# naiLED_eagle.net
KiCad netlist of a schematic drawn in EAGLE
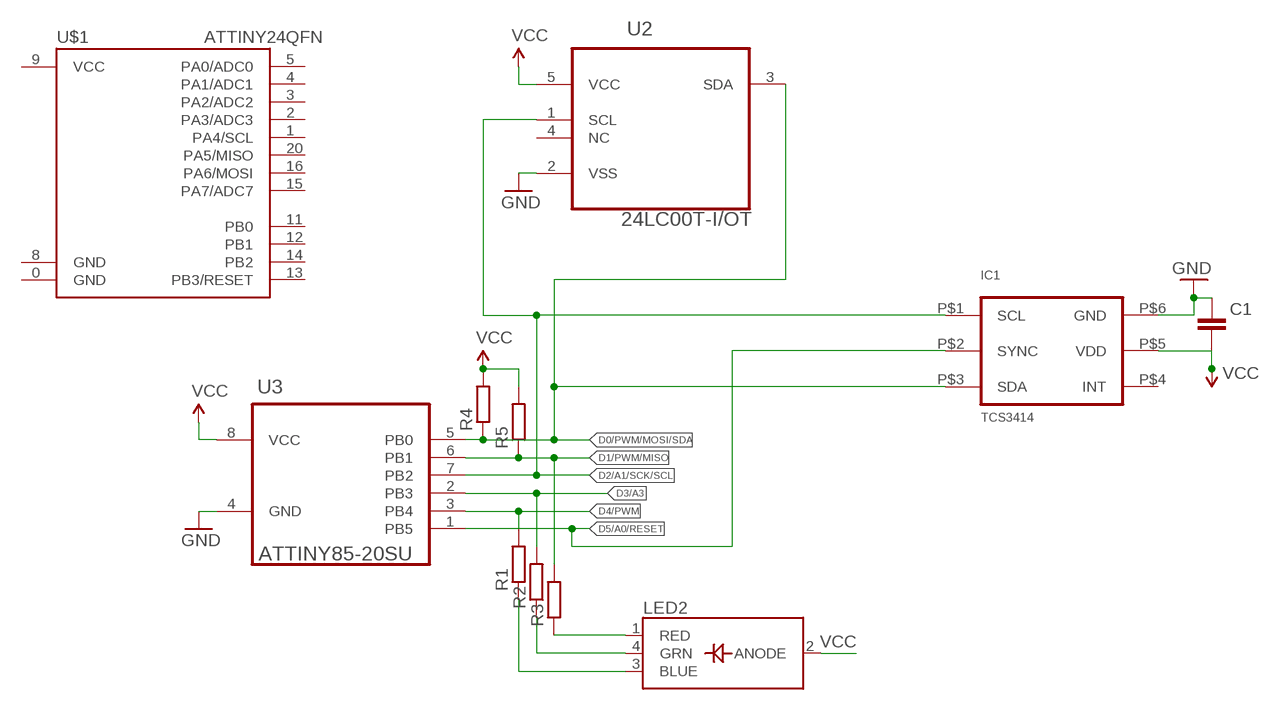
[diagram p0: schematic, sheet 1]

(export (version "E")
  (design (tool "Eeschema 10.0.6"))
  (components
    (comp (ref "C1")
      (value "CAPACITOR_NPOL-0402")
      (footprint "eagle-import:C402")
      (libsource (lib "eagle-import") (part "CAPACITOR_NPOL-0402"))
    )
    (comp (ref "IC1")
      (value "TCS3414")
      (footprint "eagle-import:DFN-6PIN")
      (libsource (lib "eagle-import") (part "TCS3414"))
    )
    (comp (ref "LED2")
      (value "LED_RGB_PLCC4")
      (footprint "eagle-import:RGBLED_PLCC4")
      (libsource (lib "eagle-import") (part "LED_RGB_PLCC4"))
    )
    (comp (ref "R1")
      (value "RESISTOR-0402")
      (footprint "eagle-import:R402")
      (libsource (lib "eagle-import") (part "RESISTOR-0402"))
    )
    (comp (ref "R2")
      (value "RESISTOR-0402")
      (footprint "eagle-import:R402")
      (libsource (lib "eagle-import") (part "RESISTOR-0402"))
    )
    (comp (ref "R3")
      (value "RESISTOR-0402")
      (footprint "eagle-import:R402")
      (libsource (lib "eagle-import") (part "RESISTOR-0402"))
    )
    (comp (ref "R4")
      (value "RESISTOR-0402")
      (footprint "eagle-import:R402")
      (libsource (lib "eagle-import") (part "RESISTOR-0402"))
    )
    (comp (ref "R5")
      (value "RESISTOR-0402")
      (footprint "eagle-import:R402")
      (libsource (lib "eagle-import") (part "RESISTOR-0402"))
    )
    (comp (ref "U$1")
      (value "ATTINY24QFN")
      (footprint "eagle-import:QFN20")
      (libsource (lib "eagle-import") (part "ATTINY24QFN"))
    )
    (comp (ref "U2")
      (value "24LC00T-I/OT")
      (footprint "eagle-import:SOT95P290X145-5N")
      (fields (field (name "MPN") "24LC00T-I/OT "))
      (libsource (lib "eagle-import") (part "24LC00T-I/OT"))
    )
    (comp (ref "U3")
      (value "ATTINY85-20SU")
      (footprint "eagle-import:SOIC127P798X216-8N")
      (libsource (lib "eagle-import") (part "ATTINY85-20SU"))
    )
  )
  (nets
    (net (code "1") (name "D0{slash}PWM{slash}MOSI{slash}SDA") (class "Default")
      (node (ref "IC1") (pin "P$3") (pinfunction "SDA_P$3") (pintype "bidirectional"))
      (node (ref "R4") (pin "1") (pinfunction "1_1") (pintype "passive"))
      (node (ref "U2") (pin "3") (pinfunction "SDA_3") (pintype "bidirectional"))
      (node (ref "U3") (pin "5") (pinfunction "PB0_5") (pintype "bidirectional"))
    )
    (net (code "2") (name "D1{slash}PWM{slash}MISO") (class "Default")
      (node (ref "R3") (pin "2") (pinfunction "2_2") (pintype "passive"))
      (node (ref "R5") (pin "1") (pinfunction "1_1") (pintype "passive"))
      (node (ref "U3") (pin "6") (pinfunction "PB1_6") (pintype "bidirectional"))
    )
    (net (code "3") (name "D2{slash}A1{slash}SCK{slash}SCL") (class "Default")
      (node (ref "IC1") (pin "P$1") (pinfunction "SCL_P$1") (pintype "bidirectional"))
      (node (ref "U2") (pin "1") (pinfunction "SCL_1") (pintype "input"))
      (node (ref "U3") (pin "7") (pinfunction "PB2_7") (pintype "bidirectional"))
    )
    (net (code "4") (name "D3{slash}A3") (class "Default")
      (node (ref "R2") (pin "2") (pinfunction "2_2") (pintype "passive"))
      (node (ref "U3") (pin "2") (pinfunction "PB3_2") (pintype "bidirectional"))
    )
    (net (code "5") (name "D4{slash}PWM") (class "Default")
      (node (ref "R1") (pin "2") (pinfunction "2_2") (pintype "passive"))
      (node (ref "U3") (pin "3") (pinfunction "PB4_3") (pintype "bidirectional"))
    )
    (net (code "6") (name "D5{slash}A0{slash}RESET") (class "Default")
      (node (ref "IC1") (pin "P$2") (pinfunction "SYNC_P$2") (pintype "bidirectional"))
      (node (ref "U3") (pin "1") (pinfunction "PB5_1") (pintype "bidirectional"))
    )
    (net (code "7") (name "GND") (class "Default")
      (node (ref "C1") (pin "2") (pinfunction "2_2") (pintype "passive"))
      (node (ref "IC1") (pin "P$6") (pinfunction "GND_P$6") (pintype "bidirectional"))
      (node (ref "U2") (pin "2") (pinfunction "VSS_2") (pintype "passive"))
      (node (ref "U3") (pin "4") (pinfunction "GND_4") (pintype "passive"))
    )
    (net (code "8") (name "Net-(LED2-BLUE)") (class "Default")
      (node (ref "LED2") (pin "3") (pinfunction "BLUE_3") (pintype "bidirectional"))
      (node (ref "R1") (pin "1") (pinfunction "1_1") (pintype "passive"))
    )
    (net (code "9") (name "Net-(LED2-GRN)") (class "Default")
      (node (ref "LED2") (pin "4") (pinfunction "GRN_4") (pintype "bidirectional"))
      (node (ref "R2") (pin "1") (pinfunction "1_1") (pintype "passive"))
    )
    (net (code "10") (name "Net-(LED2-RED)") (class "Default")
      (node (ref "LED2") (pin "1") (pinfunction "RED_1") (pintype "bidirectional"))
      (node (ref "R3") (pin "1") (pinfunction "1_1") (pintype "passive"))
    )
    (net (code "11") (name "VCC") (class "Default")
      (node (ref "C1") (pin "1") (pinfunction "1_1") (pintype "passive"))
      (node (ref "IC1") (pin "P$5") (pinfunction "VDD_P$5") (pintype "bidirectional"))
      (node (ref "LED2") (pin "2") (pinfunction "ANODE_2") (pintype "power_in"))
      (node (ref "R4") (pin "2") (pinfunction "2_2") (pintype "passive"))
      (node (ref "R5") (pin "2") (pinfunction "2_2") (pintype "passive"))
      (node (ref "U2") (pin "5") (pinfunction "VCC_5") (pintype "power_in"))
      (node (ref "U3") (pin "8") (pinfunction "VCC_8") (pintype "power_in"))
    )
    (net (code "12") (name "unconnected-(IC1-INT-PadP$4)") (class "Default")
      (node (ref "IC1") (pin "P$4") (pinfunction "INT_P$4") (pintype "bidirectional"))
    )
    (net (code "13") (name "unconnected-(U$1-GND-Pad0)") (class "Default")
      (node (ref "U$1") (pin "0") (pinfunction "GND_0") (pintype "bidirectional"))
    )
    (net (code "14") (name "unconnected-(U$1-GND-Pad8)") (class "Default")
      (node (ref "U$1") (pin "8") (pinfunction "GND_8") (pintype "bidirectional"))
    )
    (net (code "15") (name "unconnected-(U$1-PA0{slash}ADC0-Pad5)") (class "Default")
      (node (ref "U$1") (pin "5") (pinfunction "PA0/ADC0_5") (pintype "bidirectional"))
    )
    (net (code "16") (name "unconnected-(U$1-PA1{slash}ADC1-Pad4)") (class "Default")
      (node (ref "U$1") (pin "4") (pinfunction "PA1/ADC1_4") (pintype "bidirectional"))
    )
    (net (code "17") (name "unconnected-(U$1-PA2{slash}ADC2-Pad3)") (class "Default")
      (node (ref "U$1") (pin "3") (pinfunction "PA2/ADC2_3") (pintype "bidirectional"))
    )
    (net (code "18") (name "unconnected-(U$1-PA3{slash}ADC3-Pad2)") (class "Default")
      (node (ref "U$1") (pin "2") (pinfunction "PA3/ADC3_2") (pintype "bidirectional"))
    )
    (net (code "19") (name "unconnected-(U$1-PA4{slash}SCL-Pad1)") (class "Default")
      (node (ref "U$1") (pin "1") (pinfunction "PA4/SCL_1") (pintype "bidirectional"))
    )
    (net (code "20") (name "unconnected-(U$1-PA5{slash}MISO-Pad20)") (class "Default")
      (node (ref "U$1") (pin "20") (pinfunction "PA5/MISO_20") (pintype "bidirectional"))
    )
    (net (code "21") (name "unconnected-(U$1-PA6{slash}MOSI-Pad16)") (class "Default")
      (node (ref "U$1") (pin "16") (pinfunction "PA6/MOSI_16") (pintype "bidirectional"))
    )
    (net (code "22") (name "unconnected-(U$1-PA7{slash}ADC7-Pad15)") (class "Default")
      (node (ref "U$1") (pin "15") (pinfunction "PA7/ADC7_15") (pintype "bidirectional"))
    )
    (net (code "23") (name "unconnected-(U$1-PB0-Pad11)") (class "Default")
      (node (ref "U$1") (pin "11") (pinfunction "PB0_11") (pintype "bidirectional"))
    )
    (net (code "24") (name "unconnected-(U$1-PB1-Pad12)") (class "Default")
      (node (ref "U$1") (pin "12") (pinfunction "PB1_12") (pintype "bidirectional"))
    )
    (net (code "25") (name "unconnected-(U$1-PB2-Pad14)") (class "Default")
      (node (ref "U$1") (pin "14") (pinfunction "PB2_14") (pintype "bidirectional"))
    )
    (net (code "26") (name "unconnected-(U$1-PB3{slash}RESET-Pad13)") (class "Default")
      (node (ref "U$1") (pin "13") (pinfunction "PB3/RESET_13") (pintype "bidirectional"))
    )
    (net (code "27") (name "unconnected-(U$1-VCC-Pad9)") (class "Default")
      (node (ref "U$1") (pin "9") (pinfunction "VCC_9") (pintype "bidirectional"))
    )
    (net (code "28") (name "unconnected-(U2-NC-Pad4)") (class "Default")
      (node (ref "U2") (pin "4") (pinfunction "NC_4") (pintype "input"))
    )
  )
)
